# schematic_1.net
KiCad netlist of a schematic drawn in Altium Designer
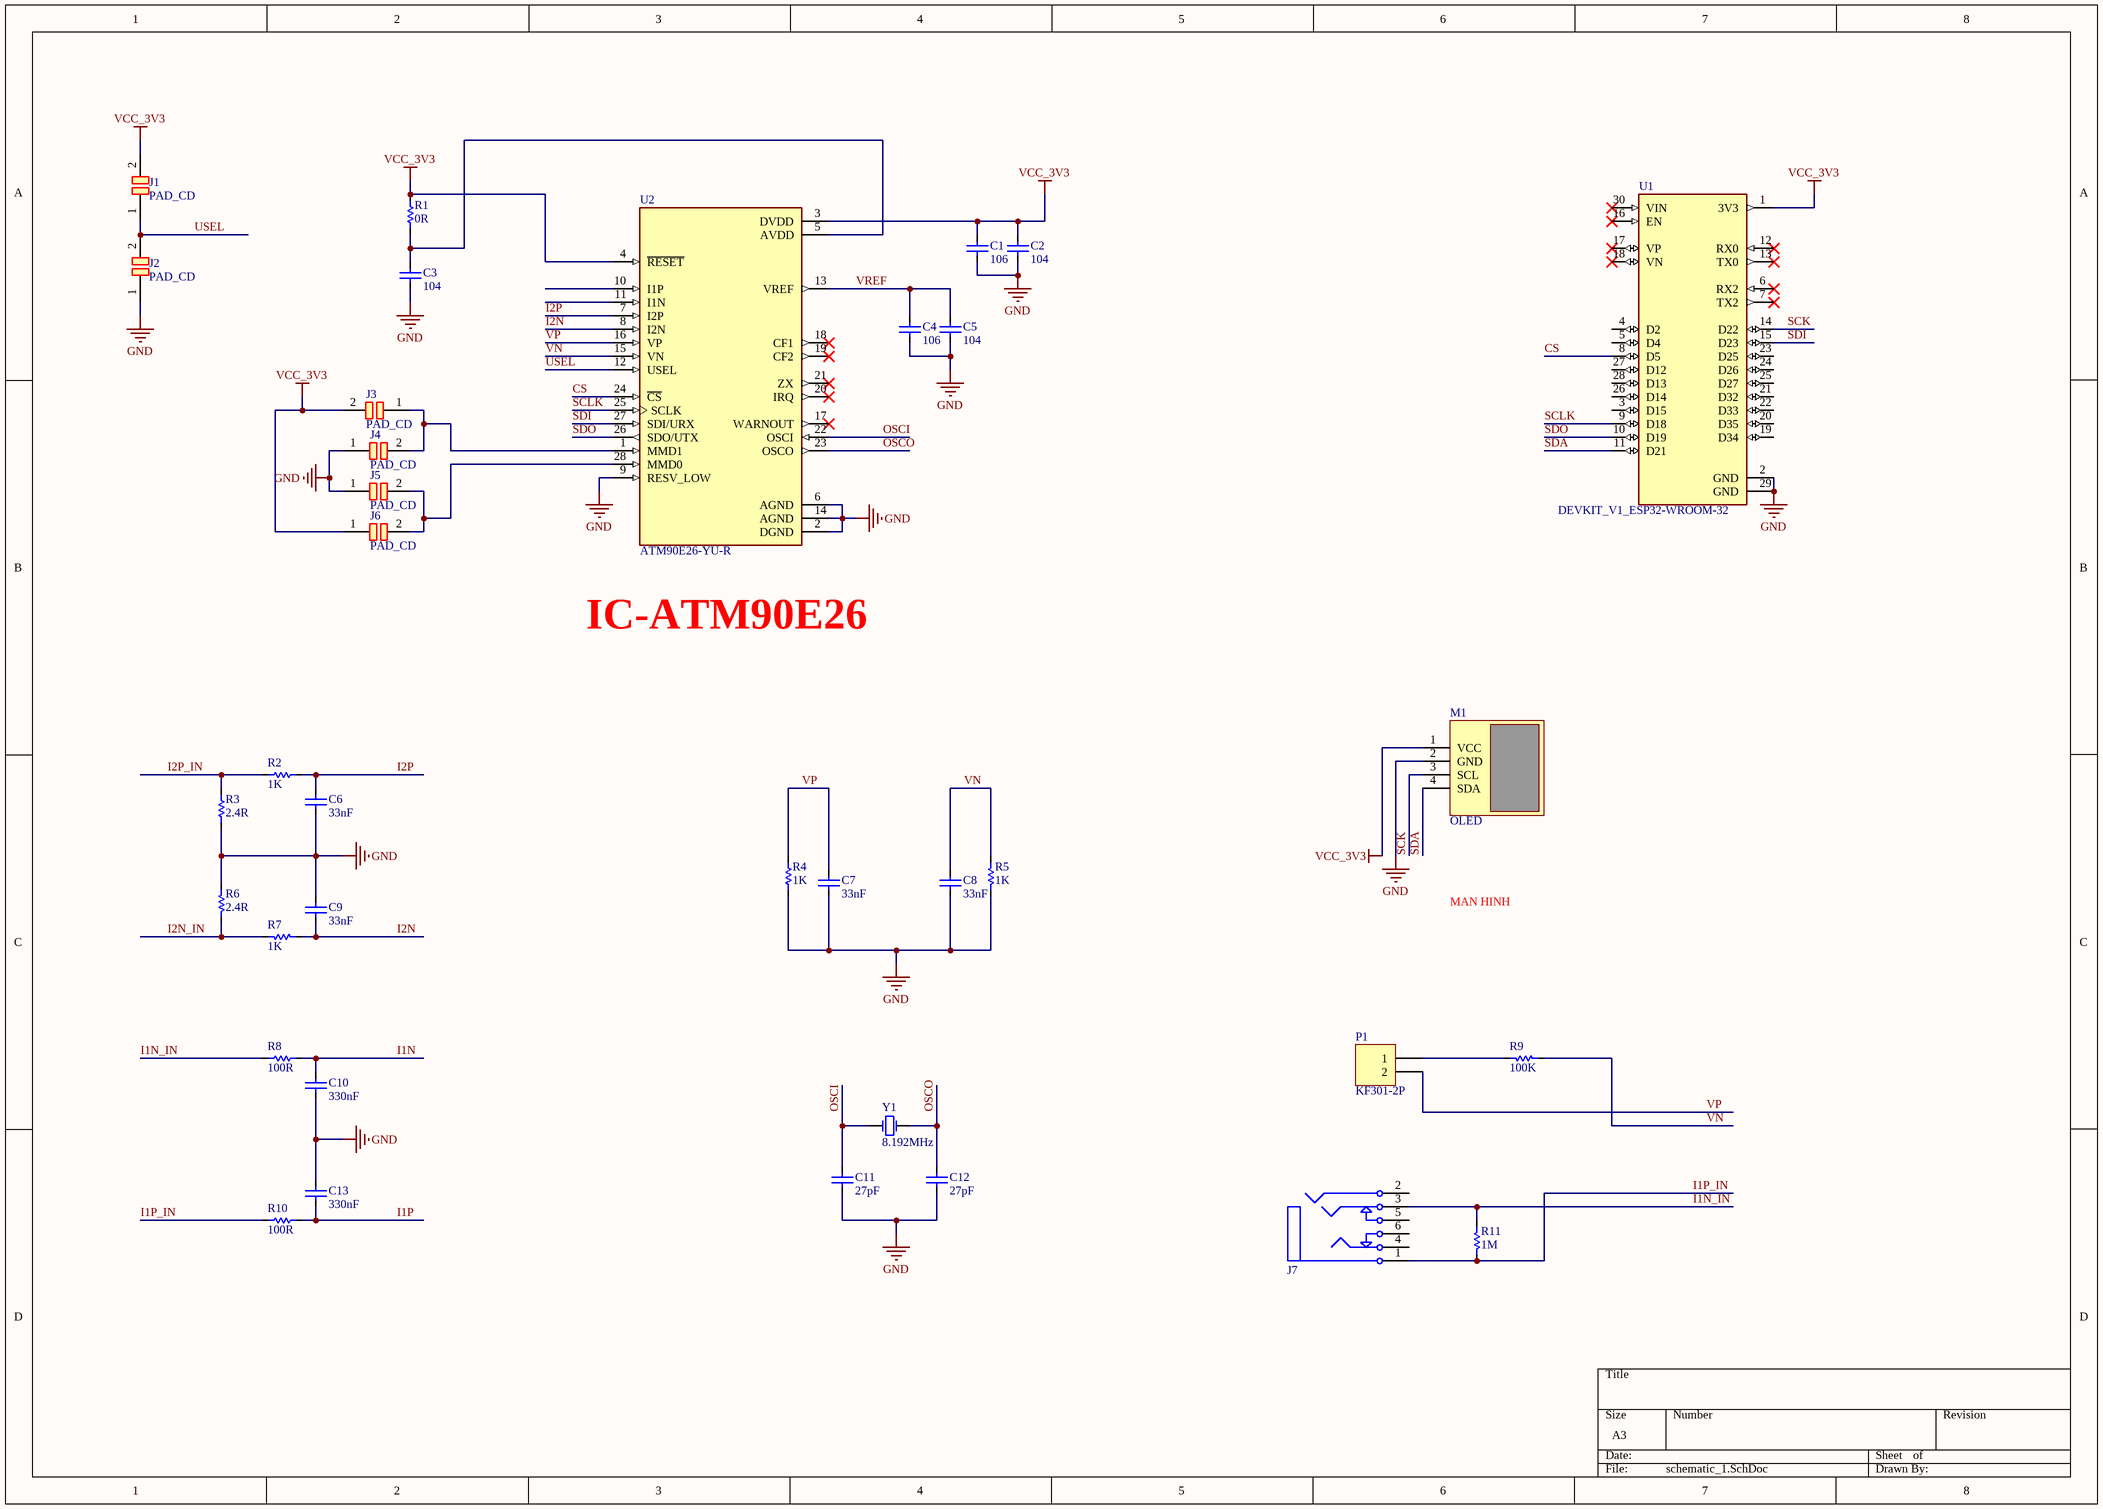
[diagram p0: schematic_1.SchDoc]

(export (version "E")
  (design (tool "Eeschema 10.0.6"))
  (components
    (comp (ref "C1")
      (value "106")
      (footprint "CAP-1206")
      (libsource (lib "Capacitors 1206-Smile-Lib") (part "CAP CER 1206 106 10V"))
    )
    (comp (ref "C2")
      (value "104")
      (footprint "CAP-0805")
      (description "*uF *V Ceramic Capacitor 0805 (2012 Metric)")
      (libsource (lib "Capacitors 0805-Smile-Lib") (part "CAP CER 0805"))
    )
    (comp (ref "C3")
      (value "104")
      (footprint "CAP-0805")
      (description "*uF *V Ceramic Capacitor 0805 (2012 Metric)")
      (libsource (lib "Capacitors 0805-Smile-Lib") (part "CAP CER 0805"))
    )
    (comp (ref "C4")
      (value "106")
      (footprint "CAP-1206")
      (libsource (lib "Capacitors 1206-Smile-Lib") (part "CAP CER 1206 106 10V"))
    )
    (comp (ref "C5")
      (value "104")
      (footprint "CAP-0805")
      (description "*uF *V Ceramic Capacitor 0805 (2012 Metric)")
      (libsource (lib "Capacitors 0805-Smile-Lib") (part "CAP CER 0805"))
    )
    (comp (ref "C6")
      (value "33nF")
      (footprint "CAP-0805")
      (description "*uF *V Ceramic Capacitor 0805 (2012 Metric)")
      (libsource (lib "Capacitors 0805-Smile-Lib") (part "CAP CER 0805"))
    )
    (comp (ref "C7")
      (value "33nF")
      (footprint "CAP-0805")
      (description "*uF *V Ceramic Capacitor 0805 (2012 Metric)")
      (libsource (lib "Capacitors 0805-Smile-Lib") (part "CAP CER 0805"))
    )
    (comp (ref "C8")
      (value "33nF")
      (footprint "CAP-0805")
      (description "*uF *V Ceramic Capacitor 0805 (2012 Metric)")
      (libsource (lib "Capacitors 0805-Smile-Lib") (part "CAP CER 0805"))
    )
    (comp (ref "C9")
      (value "33nF")
      (footprint "CAP-0805")
      (description "*uF *V Ceramic Capacitor 0805 (2012 Metric)")
      (libsource (lib "Capacitors 0805-Smile-Lib") (part "CAP CER 0805"))
    )
    (comp (ref "C10")
      (value "330nF")
      (footprint "CAP-0805")
      (description "*uF *V Ceramic Capacitor 0805 (2012 Metric)")
      (libsource (lib "Capacitors 0805-Smile-Lib") (part "CAP CER 0805"))
    )
    (comp (ref "C11")
      (value "27pF")
      (footprint "CAP-0805")
      (description "*uF *V Ceramic Capacitor 0805 (2012 Metric)")
      (libsource (lib "Capacitors 0805-Smile-Lib") (part "CAP CER 0805"))
    )
    (comp (ref "C12")
      (value "27pF")
      (footprint "CAP-0805")
      (description "*uF *V Ceramic Capacitor 0805 (2012 Metric)")
      (libsource (lib "Capacitors 0805-Smile-Lib") (part "CAP CER 0805"))
    )
    (comp (ref "C13")
      (value "330nF")
      (footprint "CAP-0805")
      (description "*uF *V Ceramic Capacitor 0805 (2012 Metric)")
      (libsource (lib "Capacitors 0805-Smile-Lib") (part "CAP CER 0805"))
    )
    (comp (ref "J1") (value "PAD_CD") (footprint "PAD_CD") (libsource (lib "") (part "PAD_CD_1")))
    (comp (ref "J2") (value "PAD_CD") (footprint "PAD_CD") (libsource (lib "") (part "PAD_CD_1")))
    (comp (ref "J3") (value "PAD_CD") (footprint "PAD_CD") (libsource (lib "BM_Sound") (part "PAD_CD")))
    (comp (ref "J4") (value "PAD_CD") (footprint "PAD_CD") (libsource (lib "") (part "PAD_CD_2")))
    (comp (ref "J5") (value "PAD_CD") (footprint "PAD_CD") (libsource (lib "") (part "PAD_CD_2")))
    (comp (ref "J6") (value "PAD_CD") (footprint "PAD_CD") (libsource (lib "") (part "PAD_CD_2")))
    (comp (ref "J7")
      (value "PJ342")
      (footprint "PJ-342")
      (libsource (lib "Audio Jack-Smile-Lib") (part "PJ342-Phone Jack"))
    )
    (comp (ref "M1")
      (value "OLED")
      (footprint "OLED 0.96 I2C")
      (libsource (lib "Modules Smile Lib") (part "OLED 0.96 I2C"))
    )
    (comp (ref "P1")
      (value "KF301-2P")
      (footprint "KF301-2P")
      (libsource (lib "KF301-Connector-Smile-Lib") (part "KF301-2P"))
    )
    (comp (ref "R1")
      (value "0R")
      (footprint "R-0805")
      (description "No Solder Or Re-Calculated")
      (libsource (lib "RES-0805-Smile-Lib") (part "R 0805"))
    )
    (comp (ref "R2")
      (value "1K")
      (footprint "R-0805")
      (description "No Solder Or Re-Calculated")
      (libsource (lib "RES-0805-Smile-Lib") (part "R 0805"))
    )
    (comp (ref "R3")
      (value "2.4R")
      (footprint "R-0805")
      (description "No Solder Or Re-Calculated")
      (libsource (lib "RES-0805-Smile-Lib") (part "R 0805"))
    )
    (comp (ref "R4")
      (value "1K")
      (footprint "R-0805")
      (description "No Solder Or Re-Calculated")
      (libsource (lib "RES-0805-Smile-Lib") (part "R 0805"))
    )
    (comp (ref "R5")
      (value "1K")
      (footprint "R-0805")
      (description "No Solder Or Re-Calculated")
      (libsource (lib "RES-0805-Smile-Lib") (part "R 0805"))
    )
    (comp (ref "R6")
      (value "2.4R")
      (footprint "R-0805")
      (description "No Solder Or Re-Calculated")
      (libsource (lib "RES-0805-Smile-Lib") (part "R 0805"))
    )
    (comp (ref "R7")
      (value "1K")
      (footprint "R-0805")
      (description "No Solder Or Re-Calculated")
      (libsource (lib "RES-0805-Smile-Lib") (part "R 0805"))
    )
    (comp (ref "R8")
      (value "100R")
      (footprint "R-0805")
      (description "No Solder Or Re-Calculated")
      (libsource (lib "RES-0805-Smile-Lib") (part "R 0805"))
    )
    (comp (ref "R9")
      (value "100K")
      (footprint "R-0805")
      (description "No Solder Or Re-Calculated")
      (libsource (lib "RES-0805-Smile-Lib") (part "R 0805"))
    )
    (comp (ref "R10")
      (value "100R")
      (footprint "R-0805")
      (description "No Solder Or Re-Calculated")
      (libsource (lib "RES-0805-Smile-Lib") (part "R 0805"))
    )
    (comp (ref "R11")
      (value "1M")
      (footprint "R-0805")
      (description "No Solder Or Re-Calculated")
      (libsource (lib "RES-0805-Smile-Lib") (part "R 0805"))
    )
    (comp (ref "U1")
      (value "DEVKIT_V1_ESP32-WROOM-32")
      (footprint "MODULE_DEVKIT_V1_ESP32-WROOM-32")
      (description "WROOM-32 Development Board ESP32 ESP-32S WiFi Bluetooth Dev Module")
      (fields (field (name "MF") "Do it") (field (name "MP") "DEVKIT V1 ESP32-WROOM-32"))
      (libsource (lib "DEVKIT_V1_ESP32-WROOM-32") (part "DEVKIT_V1_ESP32-WROOM-32"))
    )
    (comp (ref "U2")
      (value "ATM90E26-YU-R")
      (footprint "SOP65P780X200-28N")
      (description "IC ENERGY METER 1.8V/3V 28SSOP")
      (fields (field (name "MF") "Microchip"))
      (libsource (lib "ATM90E26-YU-R") (part "ATM90E26-YU-R"))
    )
    (comp (ref "Y1")
      (value "8.192MHz")
      (footprint "CRYSTAL-49S")
      (description "Crystal 49S Through Hole")
      (libsource (lib "Crystal and Oscillator-Smile-Lib") (part "CRYSTAL-49S"))
    )
  )
  (nets
    (net (code "1") (name "/CS") (class "Default")
      (node (ref "U1") (pin "8") (pinfunction "D5_8") (pintype "bidirectional"))
      (node (ref "U2") (pin "24") (pinfunction "~{CS}_24") (pintype "input"))
    )
    (net (code "2") (name "/I1N") (class "Default")
      (node (ref "C10") (pin "1") (pinfunction "1_1") (pintype "passive"))
      (node (ref "R8") (pin "1") (pinfunction "1_1") (pintype "passive"))
    )
    (net (code "3") (name "/I1N_IN") (class "Default")
      (node (ref "J7") (pin "3") (pinfunction "3_3") (pintype "passive"))
      (node (ref "R11") (pin "2") (pinfunction "2_2") (pintype "passive"))
      (node (ref "R8") (pin "2") (pinfunction "2_2") (pintype "passive"))
    )
    (net (code "4") (name "/I1P") (class "Default")
      (node (ref "C13") (pin "1") (pinfunction "1_1") (pintype "passive"))
      (node (ref "R10") (pin "1") (pinfunction "1_1") (pintype "passive"))
    )
    (net (code "5") (name "/I1P_IN") (class "Default")
      (node (ref "J7") (pin "1") (pinfunction "1_1") (pintype "passive"))
      (node (ref "R10") (pin "2") (pinfunction "2_2") (pintype "passive"))
      (node (ref "R11") (pin "1") (pinfunction "1_1") (pintype "passive"))
    )
    (net (code "6") (name "/I2N") (class "Default")
      (node (ref "C9") (pin "1") (pinfunction "1_1") (pintype "passive"))
      (node (ref "R7") (pin "1") (pinfunction "1_1") (pintype "passive"))
      (node (ref "U2") (pin "8") (pinfunction "I2N_8") (pintype "input"))
    )
    (net (code "7") (name "/I2N_IN") (class "Default")
      (node (ref "R6") (pin "1") (pinfunction "1_1") (pintype "passive"))
      (node (ref "R7") (pin "2") (pinfunction "2_2") (pintype "passive"))
    )
    (net (code "8") (name "/I2P") (class "Default")
      (node (ref "C6") (pin "1") (pinfunction "1_1") (pintype "passive"))
      (node (ref "R2") (pin "1") (pinfunction "1_1") (pintype "passive"))
      (node (ref "U2") (pin "7") (pinfunction "I2P_7") (pintype "input"))
    )
    (net (code "9") (name "/I2P_IN") (class "Default")
      (node (ref "R2") (pin "2") (pinfunction "2_2") (pintype "passive"))
      (node (ref "R3") (pin "1") (pinfunction "1_1") (pintype "passive"))
    )
    (net (code "10") (name "/OSCI") (class "Default")
      (node (ref "C11") (pin "1") (pinfunction "1_1") (pintype "passive"))
      (node (ref "U2") (pin "22") (pinfunction "OSCI_22") (pintype "input"))
      (node (ref "Y1") (pin "1") (pinfunction "OSC1_1") (pintype "passive"))
    )
    (net (code "11") (name "/OSCO") (class "Default")
      (node (ref "C12") (pin "1") (pinfunction "1_1") (pintype "passive"))
      (node (ref "U2") (pin "23") (pinfunction "OSCO_23") (pintype "output"))
      (node (ref "Y1") (pin "2") (pinfunction "OSC2_2") (pintype "passive"))
    )
    (net (code "12") (name "/SCK") (class "Default")
      (node (ref "M1") (pin "3") (pinfunction "SCL_3") (pintype "passive"))
      (node (ref "U1") (pin "14") (pinfunction "D22_14") (pintype "bidirectional"))
    )
    (net (code "13") (name "/SCLK") (class "Default")
      (node (ref "U1") (pin "9") (pinfunction "D18_9") (pintype "bidirectional"))
      (node (ref "U2") (pin "25") (pinfunction "SCLK_25") (pintype "input"))
    )
    (net (code "14") (name "/SDA") (class "Default")
      (node (ref "M1") (pin "4") (pinfunction "SDA_4") (pintype "passive"))
      (node (ref "U1") (pin "11") (pinfunction "D21_11") (pintype "bidirectional"))
    )
    (net (code "15") (name "/SDI") (class "Default")
      (node (ref "U1") (pin "15") (pinfunction "D23_15") (pintype "bidirectional"))
      (node (ref "U2") (pin "27") (pinfunction "SDI/URX_27") (pintype "input"))
    )
    (net (code "16") (name "/SDO") (class "Default")
      (node (ref "U1") (pin "10") (pinfunction "D19_10") (pintype "bidirectional"))
      (node (ref "U2") (pin "26") (pinfunction "SDO/UTX_26") (pintype "output"))
    )
    (net (code "17") (name "/USEL") (class "Default")
      (node (ref "J1") (pin "1") (pinfunction "25_1") (pintype "passive"))
      (node (ref "J2") (pin "2") (pinfunction "26_2") (pintype "passive"))
      (node (ref "U2") (pin "12") (pinfunction "USEL_12") (pintype "input"))
    )
    (net (code "18") (name "/VN") (class "Default")
      (node (ref "C8") (pin "1") (pinfunction "1_1") (pintype "passive"))
      (node (ref "R5") (pin "1") (pinfunction "1_1") (pintype "passive"))
      (node (ref "R9") (pin "2") (pinfunction "2_2") (pintype "passive"))
      (node (ref "U2") (pin "15") (pinfunction "VN_15") (pintype "input"))
    )
    (net (code "19") (name "/VP") (class "Default")
      (node (ref "C7") (pin "1") (pinfunction "1_1") (pintype "passive"))
      (node (ref "P1") (pin "2") (pinfunction "2_2") (pintype "passive"))
      (node (ref "R4") (pin "1") (pinfunction "1_1") (pintype "passive"))
      (node (ref "U2") (pin "16") (pinfunction "VP_16") (pintype "input"))
    )
    (net (code "20") (name "/VREF") (class "Default")
      (node (ref "C4") (pin "1") (pinfunction "1_1") (pintype "passive"))
      (node (ref "C5") (pin "1") (pinfunction "1_1") (pintype "passive"))
      (node (ref "U2") (pin "13") (pinfunction "VREF_13") (pintype "output"))
    )
    (net (code "21") (name "GND") (class "Default")
      (node (ref "C1") (pin "2") (pinfunction "2_2") (pintype "passive"))
      (node (ref "C10") (pin "2") (pinfunction "2_2") (pintype "passive"))
      (node (ref "C11") (pin "2") (pinfunction "2_2") (pintype "passive"))
      (node (ref "C12") (pin "2") (pinfunction "2_2") (pintype "passive"))
      (node (ref "C13") (pin "2") (pinfunction "2_2") (pintype "passive"))
      (node (ref "C2") (pin "2") (pinfunction "2_2") (pintype "passive"))
      (node (ref "C3") (pin "2") (pinfunction "2_2") (pintype "passive"))
      (node (ref "C4") (pin "2") (pinfunction "2_2") (pintype "passive"))
      (node (ref "C5") (pin "2") (pinfunction "2_2") (pintype "passive"))
      (node (ref "C6") (pin "2") (pinfunction "2_2") (pintype "passive"))
      (node (ref "C7") (pin "2") (pinfunction "2_2") (pintype "passive"))
      (node (ref "C8") (pin "2") (pinfunction "2_2") (pintype "passive"))
      (node (ref "C9") (pin "2") (pinfunction "2_2") (pintype "passive"))
      (node (ref "J2") (pin "1") (pinfunction "25_1") (pintype "passive"))
      (node (ref "J4") (pin "1") (pinfunction "25_1") (pintype "passive"))
      (node (ref "J5") (pin "1") (pinfunction "25_1") (pintype "passive"))
      (node (ref "M1") (pin "2") (pinfunction "GND_2") (pintype "passive"))
      (node (ref "R3") (pin "2") (pinfunction "2_2") (pintype "passive"))
      (node (ref "R4") (pin "2") (pinfunction "2_2") (pintype "passive"))
      (node (ref "R5") (pin "2") (pinfunction "2_2") (pintype "passive"))
      (node (ref "R6") (pin "2") (pinfunction "2_2") (pintype "passive"))
      (node (ref "U1") (pin "2") (pinfunction "GND_2") (pintype "power_in"))
      (node (ref "U1") (pin "29") (pinfunction "GND_29") (pintype "power_in"))
      (node (ref "U2") (pin "14") (pinfunction "AGND_14") (pintype "power_in"))
      (node (ref "U2") (pin "2") (pinfunction "DGND_2") (pintype "power_in"))
      (node (ref "U2") (pin "6") (pinfunction "AGND_6") (pintype "power_in"))
      (node (ref "U2") (pin "9") (pinfunction "RESV_LOW_9") (pintype "input"))
    )
    (net (code "22") (name "Net-(J3-25)") (class "Default")
      (node (ref "J3") (pin "1") (pinfunction "25_1") (pintype "passive"))
      (node (ref "J4") (pin "2") (pinfunction "26_2") (pintype "passive"))
      (node (ref "U2") (pin "1") (pinfunction "MMD1_1") (pintype "input"))
    )
    (net (code "23") (name "Net-(J5-26)") (class "Default")
      (node (ref "J5") (pin "2") (pinfunction "26_2") (pintype "passive"))
      (node (ref "J6") (pin "2") (pinfunction "26_2") (pintype "passive"))
      (node (ref "U2") (pin "28") (pinfunction "MMD0_28") (pintype "input"))
    )
    (net (code "24") (name "Net-(P1-Pad1)") (class "Default")
      (node (ref "P1") (pin "1") (pinfunction "1_1") (pintype "passive"))
      (node (ref "R9") (pin "1") (pinfunction "1_1") (pintype "passive"))
    )
    (net (code "25") (name "Net-(U2-AVDD)") (class "Default")
      (node (ref "C3") (pin "1") (pinfunction "1_1") (pintype "passive"))
      (node (ref "R1") (pin "1") (pinfunction "1_1") (pintype "passive"))
      (node (ref "U2") (pin "5") (pinfunction "AVDD_5") (pintype "power_in"))
    )
    (net (code "26") (name "VCC_3V3") (class "Default")
      (node (ref "C1") (pin "1") (pinfunction "1_1") (pintype "passive"))
      (node (ref "C2") (pin "1") (pinfunction "1_1") (pintype "passive"))
      (node (ref "J1") (pin "2") (pinfunction "26_2") (pintype "passive"))
      (node (ref "J3") (pin "2") (pinfunction "26_2") (pintype "passive"))
      (node (ref "J6") (pin "1") (pinfunction "25_1") (pintype "passive"))
      (node (ref "M1") (pin "1") (pinfunction "VCC_1") (pintype "passive"))
      (node (ref "R1") (pin "2") (pinfunction "2_2") (pintype "passive"))
      (node (ref "U1") (pin "1") (pinfunction "3V3_1") (pintype "output"))
      (node (ref "U2") (pin "3") (pinfunction "DVDD_3") (pintype "power_in"))
      (node (ref "U2") (pin "4") (pinfunction "~{RESET}_4") (pintype "input"))
    )
    (net (code "27") (name "unconnected-(J7-Pad2)") (class "Default")
      (node (ref "J7") (pin "2") (pinfunction "2_2") (pintype "passive"))
    )
    (net (code "28") (name "unconnected-(J7-Pad4)") (class "Default")
      (node (ref "J7") (pin "4") (pinfunction "4_4") (pintype "passive"))
    )
    (net (code "29") (name "unconnected-(J7-Pad5)") (class "Default")
      (node (ref "J7") (pin "5") (pinfunction "5_5") (pintype "passive"))
    )
    (net (code "30") (name "unconnected-(J7-Pad6)") (class "Default")
      (node (ref "J7") (pin "6") (pinfunction "6_6") (pintype "passive"))
    )
    (net (code "31") (name "unconnected-(U1-D2-Pad4)") (class "Default")
      (node (ref "U1") (pin "4") (pinfunction "D2_4") (pintype "bidirectional"))
    )
    (net (code "32") (name "unconnected-(U1-D4-Pad5)") (class "Default")
      (node (ref "U1") (pin "5") (pinfunction "D4_5") (pintype "bidirectional"))
    )
    (net (code "33") (name "unconnected-(U1-D12-Pad27)") (class "Default")
      (node (ref "U1") (pin "27") (pinfunction "D12_27") (pintype "bidirectional"))
    )
    (net (code "34") (name "unconnected-(U1-D13-Pad28)") (class "Default")
      (node (ref "U1") (pin "28") (pinfunction "D13_28") (pintype "bidirectional"))
    )
    (net (code "35") (name "unconnected-(U1-D14-Pad26)") (class "Default")
      (node (ref "U1") (pin "26") (pinfunction "D14_26") (pintype "bidirectional"))
    )
    (net (code "36") (name "unconnected-(U1-D15-Pad3)") (class "Default")
      (node (ref "U1") (pin "3") (pinfunction "D15_3") (pintype "bidirectional"))
    )
    (net (code "37") (name "unconnected-(U1-D25-Pad23)") (class "Default")
      (node (ref "U1") (pin "23") (pinfunction "D25_23") (pintype "bidirectional"))
    )
    (net (code "38") (name "unconnected-(U1-D26-Pad24)") (class "Default")
      (node (ref "U1") (pin "24") (pinfunction "D26_24") (pintype "bidirectional"))
    )
    (net (code "39") (name "unconnected-(U1-D27-Pad25)") (class "Default")
      (node (ref "U1") (pin "25") (pinfunction "D27_25") (pintype "bidirectional"))
    )
    (net (code "40") (name "unconnected-(U1-D32-Pad21)") (class "Default")
      (node (ref "U1") (pin "21") (pinfunction "D32_21") (pintype "bidirectional"))
    )
    (net (code "41") (name "unconnected-(U1-D33-Pad22)") (class "Default")
      (node (ref "U1") (pin "22") (pinfunction "D33_22") (pintype "bidirectional"))
    )
    (net (code "42") (name "unconnected-(U1-D34-Pad19)") (class "Default")
      (node (ref "U1") (pin "19") (pinfunction "D34_19") (pintype "bidirectional"))
    )
    (net (code "43") (name "unconnected-(U1-D35-Pad20)") (class "Default")
      (node (ref "U1") (pin "20") (pinfunction "D35_20") (pintype "bidirectional"))
    )
    (net (code "44") (name "unconnected-(U1-EN-Pad16)") (class "Default")
      (node (ref "U1") (pin "16") (pinfunction "EN_16") (pintype "input+no_connect"))
    )
    (net (code "45") (name "unconnected-(U1-RX0-Pad12)") (class "Default")
      (node (ref "U1") (pin "12") (pinfunction "RX0_12") (pintype "input+no_connect"))
    )
    (net (code "46") (name "unconnected-(U1-RX2-Pad6)") (class "Default")
      (node (ref "U1") (pin "6") (pinfunction "RX2_6") (pintype "input+no_connect"))
    )
    (net (code "47") (name "unconnected-(U1-TX0-Pad13)") (class "Default")
      (node (ref "U1") (pin "13") (pinfunction "TX0_13") (pintype "output+no_connect"))
    )
    (net (code "48") (name "unconnected-(U1-TX2-Pad7)") (class "Default")
      (node (ref "U1") (pin "7") (pinfunction "TX2_7") (pintype "output+no_connect"))
    )
    (net (code "49") (name "unconnected-(U1-VIN-Pad30)") (class "Default")
      (node (ref "U1") (pin "30") (pinfunction "VIN_30") (pintype "input+no_connect"))
    )
    (net (code "50") (name "unconnected-(U1-VN-Pad18)") (class "Default")
      (node (ref "U1") (pin "18") (pinfunction "VN_18") (pintype "bidirectional+no_connect"))
    )
    (net (code "51") (name "unconnected-(U1-VP-Pad17)") (class "Default")
      (node (ref "U1") (pin "17") (pinfunction "VP_17") (pintype "bidirectional+no_connect"))
    )
    (net (code "52") (name "unconnected-(U2-CF1-Pad18)") (class "Default")
      (node (ref "U2") (pin "18") (pinfunction "CF1_18") (pintype "output+no_connect"))
    )
    (net (code "53") (name "unconnected-(U2-CF2-Pad19)") (class "Default")
      (node (ref "U2") (pin "19") (pinfunction "CF2_19") (pintype "output+no_connect"))
    )
    (net (code "54") (name "unconnected-(U2-I1N-Pad11)") (class "Default")
      (node (ref "U2") (pin "11") (pinfunction "I1N_11") (pintype "input"))
    )
    (net (code "55") (name "unconnected-(U2-I1P-Pad10)") (class "Default")
      (node (ref "U2") (pin "10") (pinfunction "I1P_10") (pintype "input"))
    )
    (net (code "56") (name "unconnected-(U2-IRQ-Pad20)") (class "Default")
      (node (ref "U2") (pin "20") (pinfunction "IRQ_20") (pintype "output+no_connect"))
    )
    (net (code "57") (name "unconnected-(U2-WARNOUT-Pad17)") (class "Default")
      (node (ref "U2") (pin "17") (pinfunction "WARNOUT_17") (pintype "output+no_connect"))
    )
    (net (code "58") (name "unconnected-(U2-ZX-Pad21)") (class "Default")
      (node (ref "U2") (pin "21") (pinfunction "ZX_21") (pintype "output+no_connect"))
    )
  )
)
